# OSO-MISC-20-002_Analog_Sensors.net
KiCad netlist of a schematic drawn in EAGLE
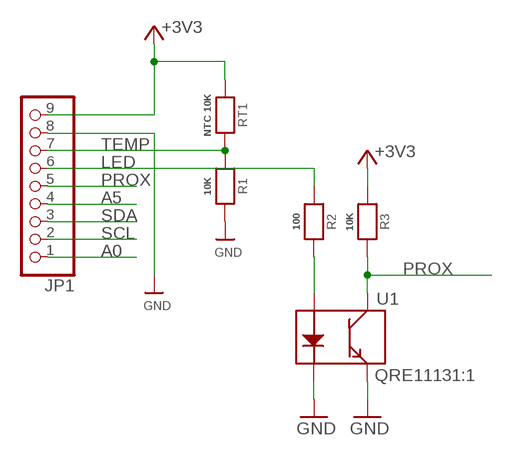
[diagram p0: schematic, sheet 1]

(export (version "E")
  (design (tool "Eeschema 10.0.6"))
  (components
    (comp (ref "JP1")
      (value "HEADER-1X9_JSTSH")
      (footprint "eagle-import:JST_SH9")
      (libsource (lib "eagle-import") (part "HEADER-1X9_JSTSH"))
    )
    (comp (ref "R1")
      (value "10K")
      (footprint "eagle-import:0805-NO")
      (libsource (lib "eagle-import") (part "RESISTOR0805_NOOUTLINE"))
    )
    (comp (ref "R2")
      (value "100")
      (footprint "eagle-import:0805-NO")
      (libsource (lib "eagle-import") (part "RESISTOR0805_NOOUTLINE"))
    )
    (comp (ref "R3")
      (value "10K")
      (footprint "eagle-import:0805-NO")
      (libsource (lib "eagle-import") (part "RESISTOR0805_NOOUTLINE"))
    )
    (comp (ref "RT1")
      (value "NTC 10K")
      (footprint "eagle-import:0805-NO")
      (libsource (lib "eagle-import") (part "RESISTOR0805_NOOUTLINE"))
    )
    (comp (ref "U1")
      (value "QRE11131:1")
      (footprint "eagle-import:QRE1113-1_1")
      (libsource (lib "eagle-import") (part "QRE11131{colon}1"))
    )
  )
  (nets
    (net (code "1") (name "+3V3") (class "Default")
      (node (ref "JP1") (pin "9") (pinfunction "9_9") (pintype "passive"))
      (node (ref "R3") (pin "1") (pinfunction "1_1") (pintype "passive"))
      (node (ref "RT1") (pin "1") (pinfunction "1_1") (pintype "passive"))
    )
    (net (code "2") (name "/A0") (class "Default")
      (node (ref "JP1") (pin "1") (pinfunction "1_1") (pintype "passive"))
    )
    (net (code "3") (name "/A5") (class "Default")
      (node (ref "JP1") (pin "4") (pinfunction "4_4") (pintype "passive"))
    )
    (net (code "4") (name "/LED") (class "Default")
      (node (ref "JP1") (pin "6") (pinfunction "6_6") (pintype "passive"))
      (node (ref "R2") (pin "1") (pinfunction "1_1") (pintype "passive"))
    )
    (net (code "5") (name "/PROX") (class "Default")
      (node (ref "JP1") (pin "5") (pinfunction "5_5") (pintype "passive"))
      (node (ref "R3") (pin "2") (pinfunction "2_2") (pintype "passive"))
      (node (ref "U1") (pin "3") (pinfunction "C_3") (pintype "bidirectional"))
    )
    (net (code "6") (name "/SCL") (class "Default")
      (node (ref "JP1") (pin "2") (pinfunction "2_2") (pintype "passive"))
    )
    (net (code "7") (name "/SDA") (class "Default")
      (node (ref "JP1") (pin "3") (pinfunction "3_3") (pintype "passive"))
    )
    (net (code "8") (name "/TEMP") (class "Default")
      (node (ref "JP1") (pin "7") (pinfunction "7_7") (pintype "passive"))
      (node (ref "R1") (pin "1") (pinfunction "1_1") (pintype "passive"))
      (node (ref "RT1") (pin "2") (pinfunction "2_2") (pintype "passive"))
    )
    (net (code "9") (name "GND") (class "Default")
      (node (ref "JP1") (pin "8") (pinfunction "8_8") (pintype "passive"))
      (node (ref "R1") (pin "2") (pinfunction "2_2") (pintype "passive"))
      (node (ref "U1") (pin "2") (pinfunction "K_2") (pintype "bidirectional"))
      (node (ref "U1") (pin "4") (pinfunction "E_4") (pintype "bidirectional"))
    )
    (net (code "10") (name "Net-(U1-A)") (class "Default")
      (node (ref "R2") (pin "2") (pinfunction "2_2") (pintype "passive"))
      (node (ref "U1") (pin "1") (pinfunction "A_1") (pintype "bidirectional"))
    )
  )
)
